# handle_board.net
KiCad netlist of a schematic drawn in EAGLE
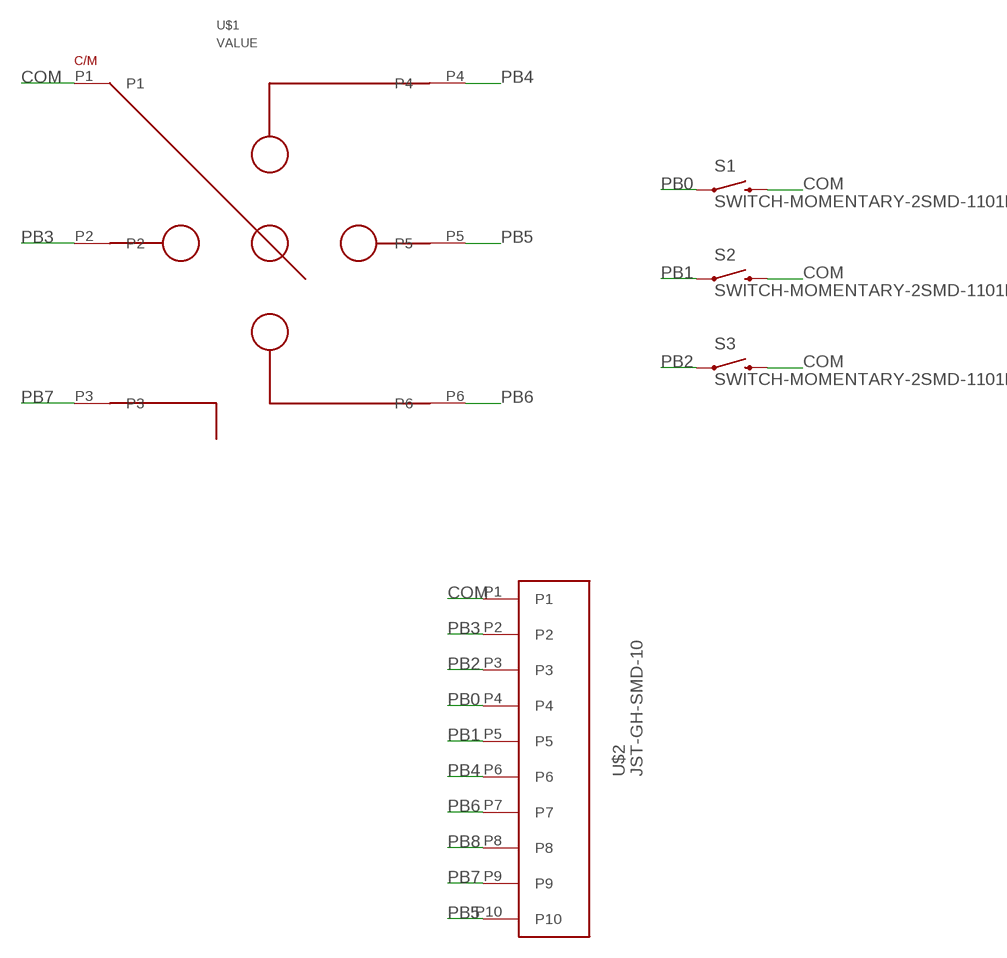
[diagram p0: schematic, sheet 1]

(export (version "E")
  (design (tool "Eeschema 10.0.6"))
  (components
    (comp (ref "S1")
      (value "SWITCH-MOMENTARY-2SMD-1101NE")
      (footprint "eagle-import:TACTILE-SWITCH-1101NE")
      (libsource (lib "eagle-import") (part "SWITCH-MOMENTARY-2SMD-1101NE"))
    )
    (comp (ref "S2")
      (value "SWITCH-MOMENTARY-2SMD-1101NE")
      (footprint "eagle-import:TACTILE-SWITCH-1101NE")
      (libsource (lib "eagle-import") (part "SWITCH-MOMENTARY-2SMD-1101NE"))
    )
    (comp (ref "S3")
      (value "SWITCH-MOMENTARY-2SMD-1101NE")
      (footprint "eagle-import:TACTILE-SWITCH-1101NE")
      (libsource (lib "eagle-import") (part "SWITCH-MOMENTARY-2SMD-1101NE"))
    )
    (comp (ref "U$1")
      (value "JS_5208_HAT")
      (footprint "eagle-import:JS_5208_HAT")
      (libsource (lib "eagle-import") (part "JS_5208_HAT"))
    )
    (comp (ref "U$2")
      (value "JST-GH-SMD-10")
      (footprint "eagle-import:JST-GH-SMD-10")
      (libsource (lib "eagle-import") (part "JST-GH-SMD-10"))
    )
  )
  (nets
    (net (code "1") (name "/COM") (class "Default")
      (node (ref "S1") (pin "2") (pinfunction "2_2") (pintype "passive"))
      (node (ref "S2") (pin "2") (pinfunction "2_2") (pintype "passive"))
      (node (ref "S3") (pin "2") (pinfunction "2_2") (pintype "passive"))
      (node (ref "U$1") (pin "P1") (pinfunction "P1_P1") (pintype "bidirectional"))
      (node (ref "U$2") (pin "P1") (pinfunction "P1_P1") (pintype "bidirectional"))
    )
    (net (code "2") (name "/PB0") (class "Default")
      (node (ref "S1") (pin "1") (pinfunction "1_1") (pintype "passive"))
      (node (ref "U$2") (pin "P4") (pinfunction "P4_P4") (pintype "bidirectional"))
    )
    (net (code "3") (name "/PB1") (class "Default")
      (node (ref "S2") (pin "1") (pinfunction "1_1") (pintype "passive"))
      (node (ref "U$2") (pin "P5") (pinfunction "P5_P5") (pintype "bidirectional"))
    )
    (net (code "4") (name "/PB2") (class "Default")
      (node (ref "S3") (pin "1") (pinfunction "1_1") (pintype "passive"))
      (node (ref "U$2") (pin "P3") (pinfunction "P3_P3") (pintype "bidirectional"))
    )
    (net (code "5") (name "/PB3") (class "Default")
      (node (ref "U$1") (pin "P2") (pinfunction "P2_P2") (pintype "bidirectional"))
      (node (ref "U$2") (pin "P2") (pinfunction "P2_P2") (pintype "bidirectional"))
    )
    (net (code "6") (name "/PB4") (class "Default")
      (node (ref "U$1") (pin "P4") (pinfunction "P4_P4") (pintype "bidirectional"))
      (node (ref "U$2") (pin "P6") (pinfunction "P6_P6") (pintype "bidirectional"))
    )
    (net (code "7") (name "/PB5") (class "Default")
      (node (ref "U$1") (pin "P5") (pinfunction "P5_P5") (pintype "bidirectional"))
      (node (ref "U$2") (pin "P10") (pinfunction "P10_P10") (pintype "bidirectional"))
    )
    (net (code "8") (name "/PB6") (class "Default")
      (node (ref "U$1") (pin "P6") (pinfunction "P6_P6") (pintype "bidirectional"))
      (node (ref "U$2") (pin "P7") (pinfunction "P7_P7") (pintype "bidirectional"))
    )
    (net (code "9") (name "/PB7") (class "Default")
      (node (ref "U$1") (pin "P3") (pinfunction "P3_P3") (pintype "bidirectional"))
      (node (ref "U$2") (pin "P9") (pinfunction "P9_P9") (pintype "bidirectional"))
    )
    (net (code "10") (name "/PB8") (class "Default")
      (node (ref "U$2") (pin "P8") (pinfunction "P8_P8") (pintype "bidirectional"))
    )
  )
)
